# motion.net
KiCad netlist of a schematic drawn in Altium Designer
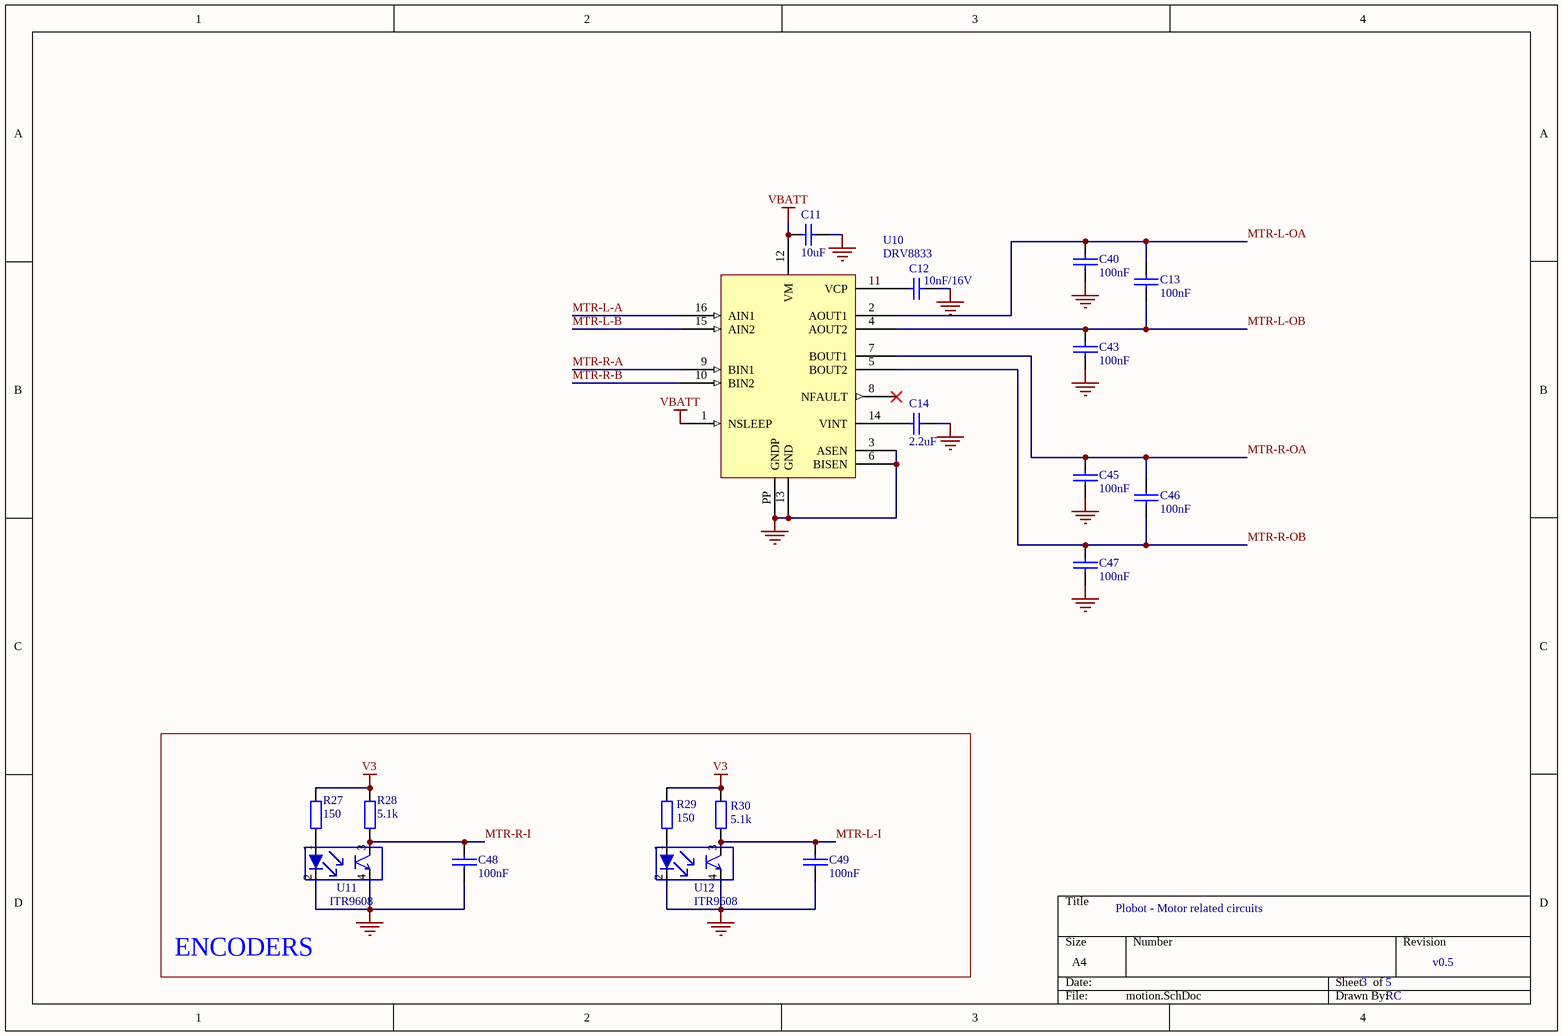
[diagram p0: motion.SchDoc]

(export (version "E")
  (design (tool "Eeschema 10.0.6"))
  (components
    (comp (ref "C11")
      (value "10uF")
      (footprint "plobot_review:CAPC3216N")
      (description "Capacitor")
      (fields (field (name "PUBLISHER") "Altium Limited"))
      (libsource (lib "main_pcb") (part "Cap_2"))
    )
    (comp (ref "C12")
      (value "10nF/16V")
      (footprint "plobot_review:CAPC2012N")
      (description "Capacitor")
      (fields (field (name "PUBLISHER") "Altium Limited"))
      (libsource (lib "") (part "Cap_1"))
    )
    (comp (ref "C13")
      (value "100nF")
      (footprint "plobot_review:CAPC1608N")
      (description "Capacitor")
      (libsource (lib "*") (part "Cap"))
    )
    (comp (ref "C14")
      (value "2.2uF")
      (footprint "plobot_review:CAPC2012N")
      (description "Capacitor")
      (fields (field (name "PUBLISHER") "Altium Limited"))
      (libsource (lib "") (part "Cap_1"))
    )
    (comp (ref "C40")
      (value "100nF")
      (footprint "plobot_review:CAPC1608N")
      (description "Capacitor")
      (libsource (lib "*") (part "Cap"))
    )
    (comp (ref "C43")
      (value "100nF")
      (footprint "plobot_review:CAPC1608N")
      (description "Capacitor")
      (libsource (lib "*") (part "Cap"))
    )
    (comp (ref "C45")
      (value "100nF")
      (footprint "plobot_review:CAPC1608N")
      (description "Capacitor")
      (libsource (lib "*") (part "Cap"))
    )
    (comp (ref "C46")
      (value "100nF")
      (footprint "plobot_review:CAPC1608N")
      (description "Capacitor")
      (libsource (lib "*") (part "Cap"))
    )
    (comp (ref "C47")
      (value "100nF")
      (footprint "plobot_review:CAPC1608N")
      (description "Capacitor")
      (libsource (lib "*") (part "Cap"))
    )
    (comp (ref "C48")
      (value "100nF")
      (footprint "plobot_review:CAPC1608N")
      (description "Capacitor")
      (libsource (lib "*") (part "Cap"))
    )
    (comp (ref "C49")
      (value "100nF")
      (footprint "plobot_review:CAPC1608N")
      (description "Capacitor")
      (libsource (lib "*") (part "Cap"))
    )
    (comp (ref "R27")
      (value "150")
      (footprint "plobot_review:RESC1608N")
      (description "Resistor")
      (fields (field (name "Comment") "1K") (field (name "PUBLISHER") "Altium Limited"))
      (libsource (lib "*") (part "Res2"))
    )
    (comp (ref "R28")
      (value "5.1k")
      (footprint "plobot_review:RESC1608N")
      (description "Resistor")
      (fields (field (name "PUBLISHER") "Altium Limited"))
      (libsource (lib "*") (part "Res2"))
    )
    (comp (ref "R29")
      (value "150")
      (footprint "plobot_review:RESC1608N")
      (description "Resistor")
      (fields (field (name "Comment") "1K") (field (name "PUBLISHER") "Altium Limited"))
      (libsource (lib "*") (part "Res2"))
    )
    (comp (ref "R30")
      (value "5.1k")
      (footprint "plobot_review:RESC1608N")
      (description "Resistor")
      (fields (field (name "PUBLISHER") "Altium Limited"))
      (libsource (lib "*") (part "Res2"))
    )
    (comp (ref "U10")
      (value "DRV8833")
      (footprint "plobot_review:DRV8833")
      (libsource (lib "components") (part "DRV8833"))
    )
    (comp (ref "U11")
      (value "ITR9608")
      (footprint "plobot_review:ITR9608")
      (libsource (lib "*") (part "ITR9608"))
    )
    (comp (ref "U12")
      (value "ITR9608")
      (footprint "plobot_review:ITR9608")
      (libsource (lib "*") (part "ITR9608"))
    )
  )
  (nets
    (net (code "1") (name "/MTR-L-A") (class "Default")
      (node (ref "U10") (pin "16") (pinfunction "AIN1_16") (pintype "input"))
    )
    (net (code "2") (name "/MTR-L-B") (class "Default")
      (node (ref "U10") (pin "15") (pinfunction "AIN2_15") (pintype "input"))
    )
    (net (code "3") (name "/MTR-L-I") (class "Default")
      (node (ref "C49") (pin "2") (pinfunction "2_2") (pintype "passive"))
      (node (ref "R30") (pin "1") (pinfunction "1_1") (pintype "passive"))
      (node (ref "U12") (pin "3") (pinfunction "COLLECTOR_3") (pintype "passive"))
    )
    (net (code "4") (name "/MTR-L-OA") (class "Default")
      (node (ref "C13") (pin "2") (pinfunction "2_2") (pintype "passive"))
      (node (ref "C40") (pin "2") (pinfunction "2_2") (pintype "passive"))
      (node (ref "U10") (pin "2") (pinfunction "AOUT1_2") (pintype "power_in"))
    )
    (net (code "5") (name "/MTR-L-OB") (class "Default")
      (node (ref "C13") (pin "1") (pinfunction "1_1") (pintype "passive"))
      (node (ref "C43") (pin "2") (pinfunction "2_2") (pintype "passive"))
      (node (ref "U10") (pin "4") (pinfunction "AOUT2_4") (pintype "power_in"))
    )
    (net (code "6") (name "/MTR-R-A") (class "Default")
      (node (ref "U10") (pin "9") (pinfunction "BIN1_9") (pintype "input"))
    )
    (net (code "7") (name "/MTR-R-B") (class "Default")
      (node (ref "U10") (pin "10") (pinfunction "BIN2_10") (pintype "input"))
    )
    (net (code "8") (name "/MTR-R-I") (class "Default")
      (node (ref "C48") (pin "2") (pinfunction "2_2") (pintype "passive"))
      (node (ref "R28") (pin "1") (pinfunction "1_1") (pintype "passive"))
      (node (ref "U11") (pin "3") (pinfunction "COLLECTOR_3") (pintype "passive"))
    )
    (net (code "9") (name "/MTR-R-OA") (class "Default")
      (node (ref "C45") (pin "2") (pinfunction "2_2") (pintype "passive"))
      (node (ref "C46") (pin "2") (pinfunction "2_2") (pintype "passive"))
      (node (ref "U10") (pin "7") (pinfunction "BOUT1_7") (pintype "power_in"))
    )
    (net (code "10") (name "/MTR-R-OB") (class "Default")
      (node (ref "C46") (pin "1") (pinfunction "1_1") (pintype "passive"))
      (node (ref "C47") (pin "2") (pinfunction "2_2") (pintype "passive"))
      (node (ref "U10") (pin "5") (pinfunction "BOUT2_5") (pintype "power_in"))
    )
    (net (code "11") (name "GND") (class "Default")
      (node (ref "C11") (pin "1") (pinfunction "1_1") (pintype "passive"))
      (node (ref "C12") (pin "1") (pinfunction "1_1") (pintype "passive"))
      (node (ref "C14") (pin "1") (pinfunction "1_1") (pintype "passive"))
      (node (ref "C40") (pin "1") (pinfunction "1_1") (pintype "passive"))
      (node (ref "C43") (pin "1") (pinfunction "1_1") (pintype "passive"))
      (node (ref "C45") (pin "1") (pinfunction "1_1") (pintype "passive"))
      (node (ref "C47") (pin "1") (pinfunction "1_1") (pintype "passive"))
      (node (ref "C48") (pin "1") (pinfunction "1_1") (pintype "passive"))
      (node (ref "C49") (pin "1") (pinfunction "1_1") (pintype "passive"))
      (node (ref "U10") (pin "13") (pinfunction "GND_13") (pintype "power_in"))
      (node (ref "U10") (pin "3") (pinfunction "ASEN_3") (pintype "power_in"))
      (node (ref "U10") (pin "6") (pinfunction "BISEN_6") (pintype "power_in"))
      (node (ref "U10") (pin "PP") (pinfunction "GNDP_PP") (pintype "power_in"))
      (node (ref "U11") (pin "2") (pinfunction "CATHODE_2") (pintype "passive"))
      (node (ref "U11") (pin "4") (pinfunction "ENITIER_4") (pintype "passive"))
      (node (ref "U12") (pin "2") (pinfunction "CATHODE_2") (pintype "passive"))
      (node (ref "U12") (pin "4") (pinfunction "ENITIER_4") (pintype "passive"))
    )
    (net (code "12") (name "Net-(U10-VCP)") (class "Default")
      (node (ref "C12") (pin "2") (pinfunction "2_2") (pintype "passive"))
      (node (ref "U10") (pin "11") (pinfunction "VCP_11") (pintype "power_in"))
    )
    (net (code "13") (name "Net-(U10-VINT)") (class "Default")
      (node (ref "C14") (pin "2") (pinfunction "2_2") (pintype "passive"))
      (node (ref "U10") (pin "14") (pinfunction "VINT_14") (pintype "power_in"))
    )
    (net (code "14") (name "Net-(U11-ANODE)") (class "Default")
      (node (ref "R27") (pin "1") (pinfunction "1_1") (pintype "passive"))
      (node (ref "U11") (pin "1") (pinfunction "ANODE_1") (pintype "passive"))
    )
    (net (code "15") (name "Net-(U12-ANODE)") (class "Default")
      (node (ref "R29") (pin "1") (pinfunction "1_1") (pintype "passive"))
      (node (ref "U12") (pin "1") (pinfunction "ANODE_1") (pintype "passive"))
    )
    (net (code "16") (name "V3") (class "Default")
      (node (ref "R27") (pin "2") (pinfunction "2_2") (pintype "passive"))
      (node (ref "R28") (pin "2") (pinfunction "2_2") (pintype "passive"))
      (node (ref "R29") (pin "2") (pinfunction "2_2") (pintype "passive"))
      (node (ref "R30") (pin "2") (pinfunction "2_2") (pintype "passive"))
    )
    (net (code "17") (name "VBATT") (class "Default")
      (node (ref "C11") (pin "2") (pinfunction "2_2") (pintype "passive"))
      (node (ref "U10") (pin "1") (pinfunction "NSLEEP_1") (pintype "input"))
      (node (ref "U10") (pin "12") (pinfunction "VM_12") (pintype "power_in"))
    )
    (net (code "18") (name "unconnected-(U10-NFAULT-Pad8)") (class "Default")
      (node (ref "U10") (pin "8") (pinfunction "NFAULT_8") (pintype "output+no_connect"))
    )
  )
)
